# AnalogSubProc.net
KiCad netlist of a schematic drawn in EAGLE
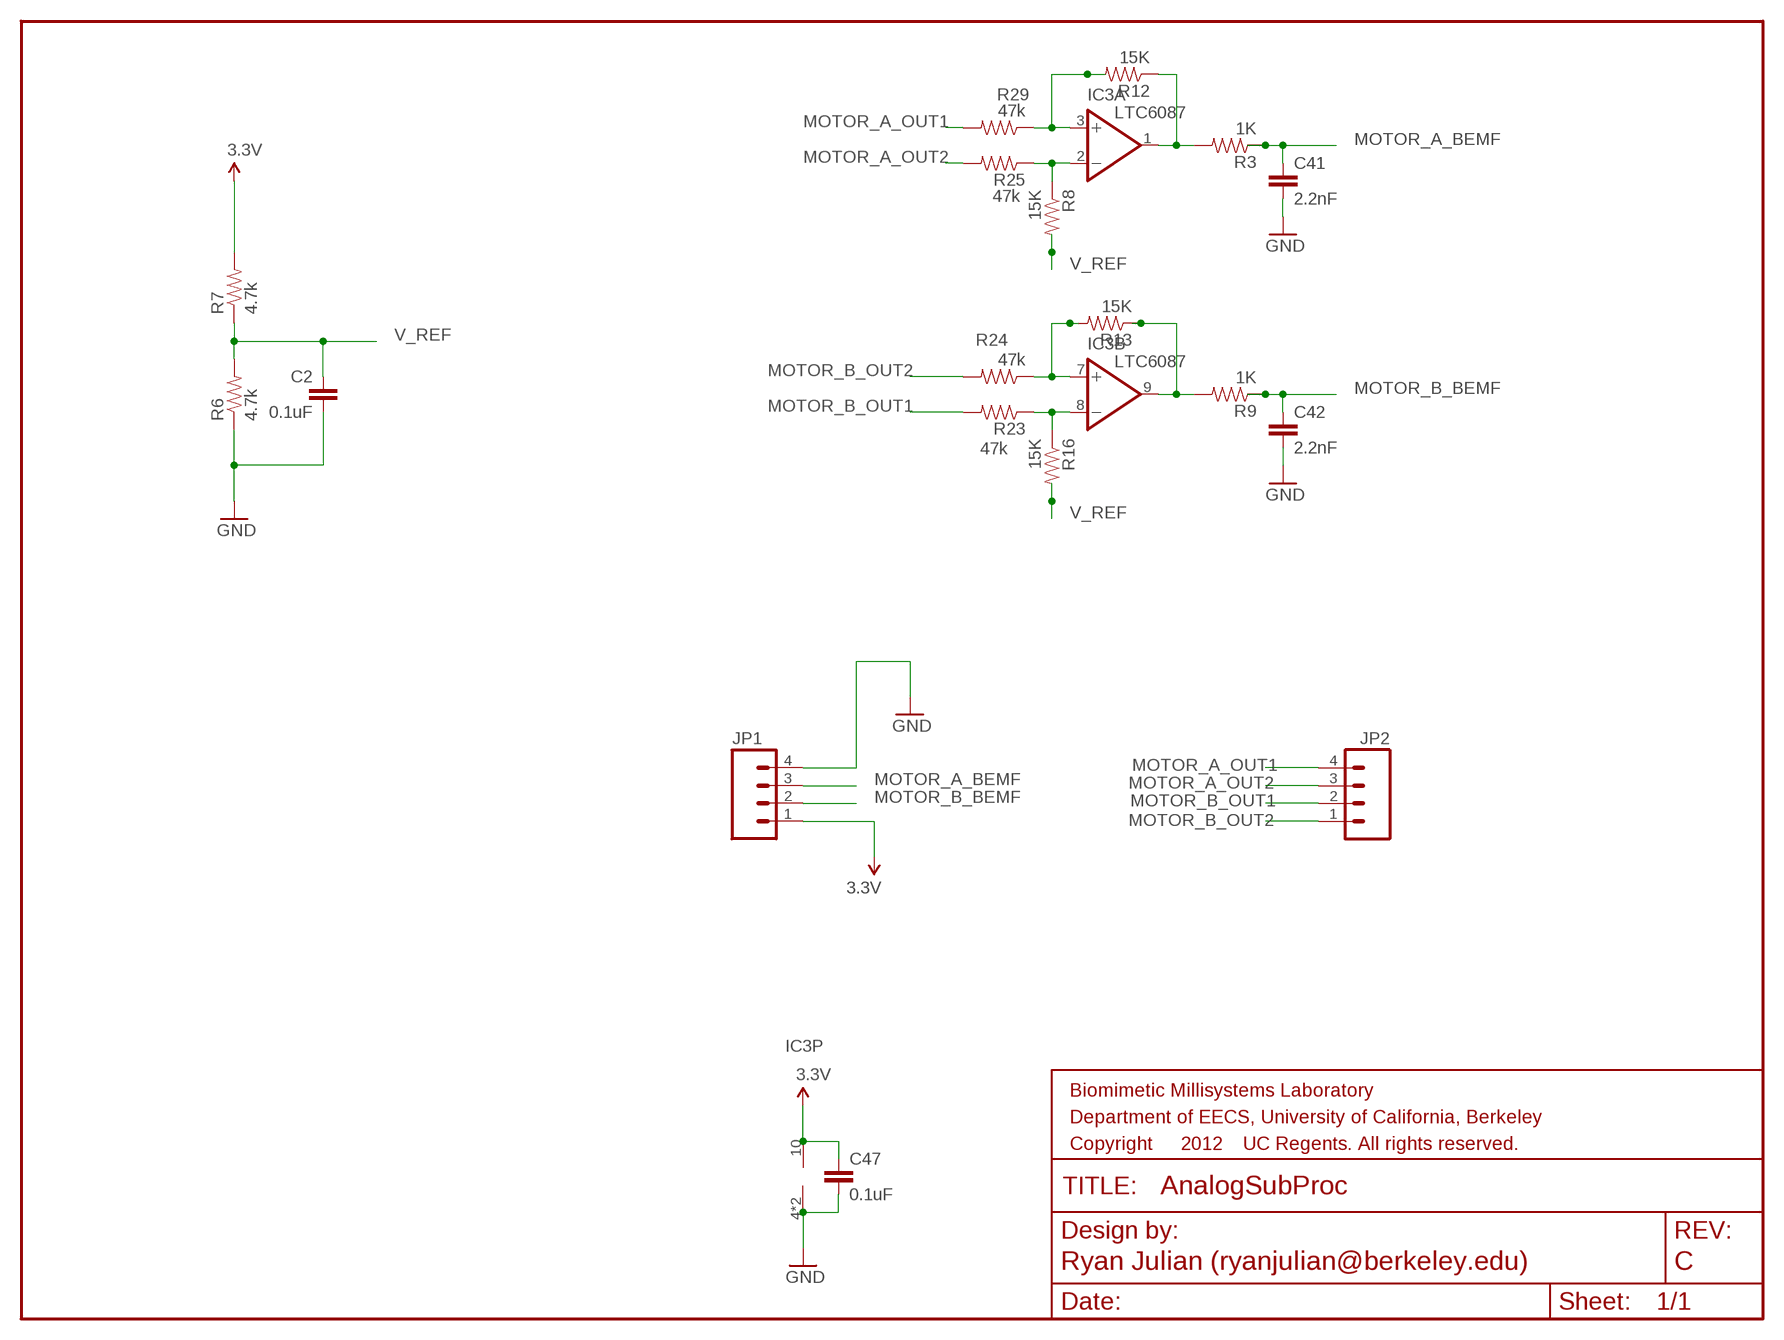
[diagram p0: schematic, sheet 1]

(export (version "E")
  (design (tool "Eeschema 10.0.6"))
  (components
    (comp (ref "C2")
      (value "0.1uF")
      (footprint "eagle-import:0402-CAP")
      (libsource (lib "eagle-import") (part "CAP0402-CAP"))
    )
    (comp (ref "C41")
      (value "2.2nF")
      (footprint "eagle-import:0402-CAP")
      (libsource (lib "eagle-import") (part "CAP0402-CAP"))
    )
    (comp (ref "C42")
      (value "2.2nF")
      (footprint "eagle-import:0402-CAP")
      (libsource (lib "eagle-import") (part "CAP0402-CAP"))
    )
    (comp (ref "C47")
      (value "0.1uF")
      (footprint "eagle-import:0402-CAP")
      (libsource (lib "eagle-import") (part "CAP0402-CAP"))
    )
    (comp (ref "IC3")
      (value "LTC6087")
      (footprint "eagle-import:DFN-10")
      (libsource (lib "eagle-import") (part "LTC6087"))
    )
    (comp (ref "JP1")
      (value "M041.27MM")
      (footprint "eagle-import:1X04-1.27MM")
      (libsource (lib "eagle-import") (part "M041.27MM"))
    )
    (comp (ref "JP2")
      (value "M041.27MM")
      (footprint "eagle-import:1X04-1.27MM")
      (libsource (lib "eagle-import") (part "M041.27MM"))
    )
    (comp (ref "R3")
      (value "1K")
      (footprint "eagle-import:0402-RES")
      (libsource (lib "eagle-import") (part "RESISTOR0402-RES"))
    )
    (comp (ref "R6")
      (value "4.7k")
      (footprint "eagle-import:0402-RES")
      (libsource (lib "eagle-import") (part "RESISTOR0402-RES"))
    )
    (comp (ref "R7")
      (value "4.7k")
      (footprint "eagle-import:0402-RES")
      (libsource (lib "eagle-import") (part "RESISTOR0402-RES"))
    )
    (comp (ref "R8")
      (value "15K")
      (footprint "eagle-import:0402-RES")
      (libsource (lib "eagle-import") (part "RESISTOR0402-RES"))
    )
    (comp (ref "R9")
      (value "1K")
      (footprint "eagle-import:0402-RES")
      (libsource (lib "eagle-import") (part "RESISTOR0402-RES"))
    )
    (comp (ref "R12")
      (value "15K")
      (footprint "eagle-import:0402-RES")
      (libsource (lib "eagle-import") (part "RESISTOR0402-RES"))
    )
    (comp (ref "R13")
      (value "15K")
      (footprint "eagle-import:0402-RES")
      (libsource (lib "eagle-import") (part "RESISTOR0402-RES"))
    )
    (comp (ref "R16")
      (value "15K")
      (footprint "eagle-import:0402-RES")
      (libsource (lib "eagle-import") (part "RESISTOR0402-RES"))
    )
    (comp (ref "R23")
      (value "47k")
      (footprint "eagle-import:0402-RES")
      (libsource (lib "eagle-import") (part "RESISTOR0402-RES"))
    )
    (comp (ref "R24")
      (value "47k")
      (footprint "eagle-import:0402-RES")
      (libsource (lib "eagle-import") (part "RESISTOR0402-RES"))
    )
    (comp (ref "R25")
      (value "47k")
      (footprint "eagle-import:0402-RES")
      (libsource (lib "eagle-import") (part "RESISTOR0402-RES"))
    )
    (comp (ref "R29")
      (value "47k")
      (footprint "eagle-import:0402-RES")
      (libsource (lib "eagle-import") (part "RESISTOR0402-RES"))
    )
  )
  (nets
    (net (code "1") (name "/MOTOR_A_BEMF") (class "Default")
      (node (ref "C41") (pin "1") (pinfunction "1_1") (pintype "passive"))
      (node (ref "JP1") (pin "3") (pinfunction "3_3") (pintype "passive"))
      (node (ref "R3") (pin "1") (pinfunction "1_1") (pintype "passive"))
    )
    (net (code "2") (name "/MOTOR_A_OUT1") (class "Default")
      (node (ref "JP2") (pin "4") (pinfunction "4_4") (pintype "passive"))
      (node (ref "R29") (pin "2") (pinfunction "2_2") (pintype "passive"))
    )
    (net (code "3") (name "/MOTOR_A_OUT2") (class "Default")
      (node (ref "JP2") (pin "3") (pinfunction "3_3") (pintype "passive"))
      (node (ref "R25") (pin "2") (pinfunction "2_2") (pintype "passive"))
    )
    (net (code "4") (name "/MOTOR_B_BEMF") (class "Default")
      (node (ref "C42") (pin "1") (pinfunction "1_1") (pintype "passive"))
      (node (ref "JP1") (pin "2") (pinfunction "2_2") (pintype "passive"))
      (node (ref "R9") (pin "1") (pinfunction "1_1") (pintype "passive"))
    )
    (net (code "5") (name "/MOTOR_B_OUT1") (class "Default")
      (node (ref "JP2") (pin "2") (pinfunction "2_2") (pintype "passive"))
      (node (ref "R23") (pin "2") (pinfunction "2_2") (pintype "passive"))
    )
    (net (code "6") (name "/MOTOR_B_OUT2") (class "Default")
      (node (ref "JP2") (pin "1") (pinfunction "1_1") (pintype "passive"))
      (node (ref "R24") (pin "2") (pinfunction "2_2") (pintype "passive"))
    )
    (net (code "7") (name "/V_REF") (class "Default")
      (node (ref "C2") (pin "1") (pinfunction "1_1") (pintype "passive"))
      (node (ref "R16") (pin "2") (pinfunction "2_2") (pintype "passive"))
      (node (ref "R6") (pin "2") (pinfunction "2_2") (pintype "passive"))
      (node (ref "R7") (pin "1") (pinfunction "1_1") (pintype "passive"))
      (node (ref "R8") (pin "2") (pinfunction "2_2") (pintype "passive"))
    )
    (net (code "8") (name "3.3V") (class "Default")
      (node (ref "C47") (pin "1") (pinfunction "1_1") (pintype "passive"))
      (node (ref "IC3") (pin "10") (pinfunction "V+_10") (pintype "power_in"))
      (node (ref "JP1") (pin "1") (pinfunction "1_1") (pintype "passive"))
      (node (ref "R7") (pin "2") (pinfunction "2_2") (pintype "passive"))
    )
    (net (code "9") (name "GND") (class "Default")
      (node (ref "C2") (pin "2") (pinfunction "2_2") (pintype "passive"))
      (node (ref "C41") (pin "2") (pinfunction "2_2") (pintype "passive"))
      (node (ref "C42") (pin "2") (pinfunction "2_2") (pintype "passive"))
      (node (ref "C47") (pin "2") (pinfunction "2_2") (pintype "passive"))
      (node (ref "IC3") (pin "4") (pinfunction "V-_4") (pintype "power_in"))
      (node (ref "IC3") (pin "PAD") (pinfunction "V-_PAD") (pintype "power_in"))
      (node (ref "JP1") (pin "4") (pinfunction "4_4") (pintype "passive"))
      (node (ref "R6") (pin "1") (pinfunction "1_1") (pintype "passive"))
    )
    (net (code "10") (name "Net-(IC3C-+IN)") (class "Default")
      (node (ref "IC3") (pin "3") (pinfunction "+IN_3") (pintype "input"))
      (node (ref "R12") (pin "2") (pinfunction "2_2") (pintype "passive"))
      (node (ref "R29") (pin "1") (pinfunction "1_1") (pintype "passive"))
    )
    (net (code "11") (name "Net-(IC3C--IN)") (class "Default")
      (node (ref "IC3") (pin "2") (pinfunction "-IN_2") (pintype "input"))
      (node (ref "R25") (pin "1") (pinfunction "1_1") (pintype "passive"))
      (node (ref "R8") (pin "1") (pinfunction "1_1") (pintype "passive"))
    )
    (net (code "12") (name "Net-(IC3C-OUT)") (class "Default")
      (node (ref "IC3") (pin "1") (pinfunction "OUT_1") (pintype "output"))
      (node (ref "R12") (pin "1") (pinfunction "1_1") (pintype "passive"))
      (node (ref "R3") (pin "2") (pinfunction "2_2") (pintype "passive"))
    )
    (net (code "13") (name "Net-(IC3D-+IN)") (class "Default")
      (node (ref "IC3") (pin "7") (pinfunction "+IN_7") (pintype "input"))
      (node (ref "R13") (pin "2") (pinfunction "2_2") (pintype "passive"))
      (node (ref "R24") (pin "1") (pinfunction "1_1") (pintype "passive"))
    )
    (net (code "14") (name "Net-(IC3D--IN)") (class "Default")
      (node (ref "IC3") (pin "8") (pinfunction "-IN_8") (pintype "input"))
      (node (ref "R16") (pin "1") (pinfunction "1_1") (pintype "passive"))
      (node (ref "R23") (pin "1") (pinfunction "1_1") (pintype "passive"))
    )
    (net (code "15") (name "Net-(IC3D-OUT)") (class "Default")
      (node (ref "IC3") (pin "9") (pinfunction "OUT_9") (pintype "output"))
      (node (ref "R13") (pin "1") (pinfunction "1_1") (pintype "passive"))
      (node (ref "R9") (pin "2") (pinfunction "2_2") (pintype "passive"))
    )
  )
)
